# ProDoc_RiscArchive_SCH.net
KiCad netlist of a schematic drawn in EasyEDA Pro
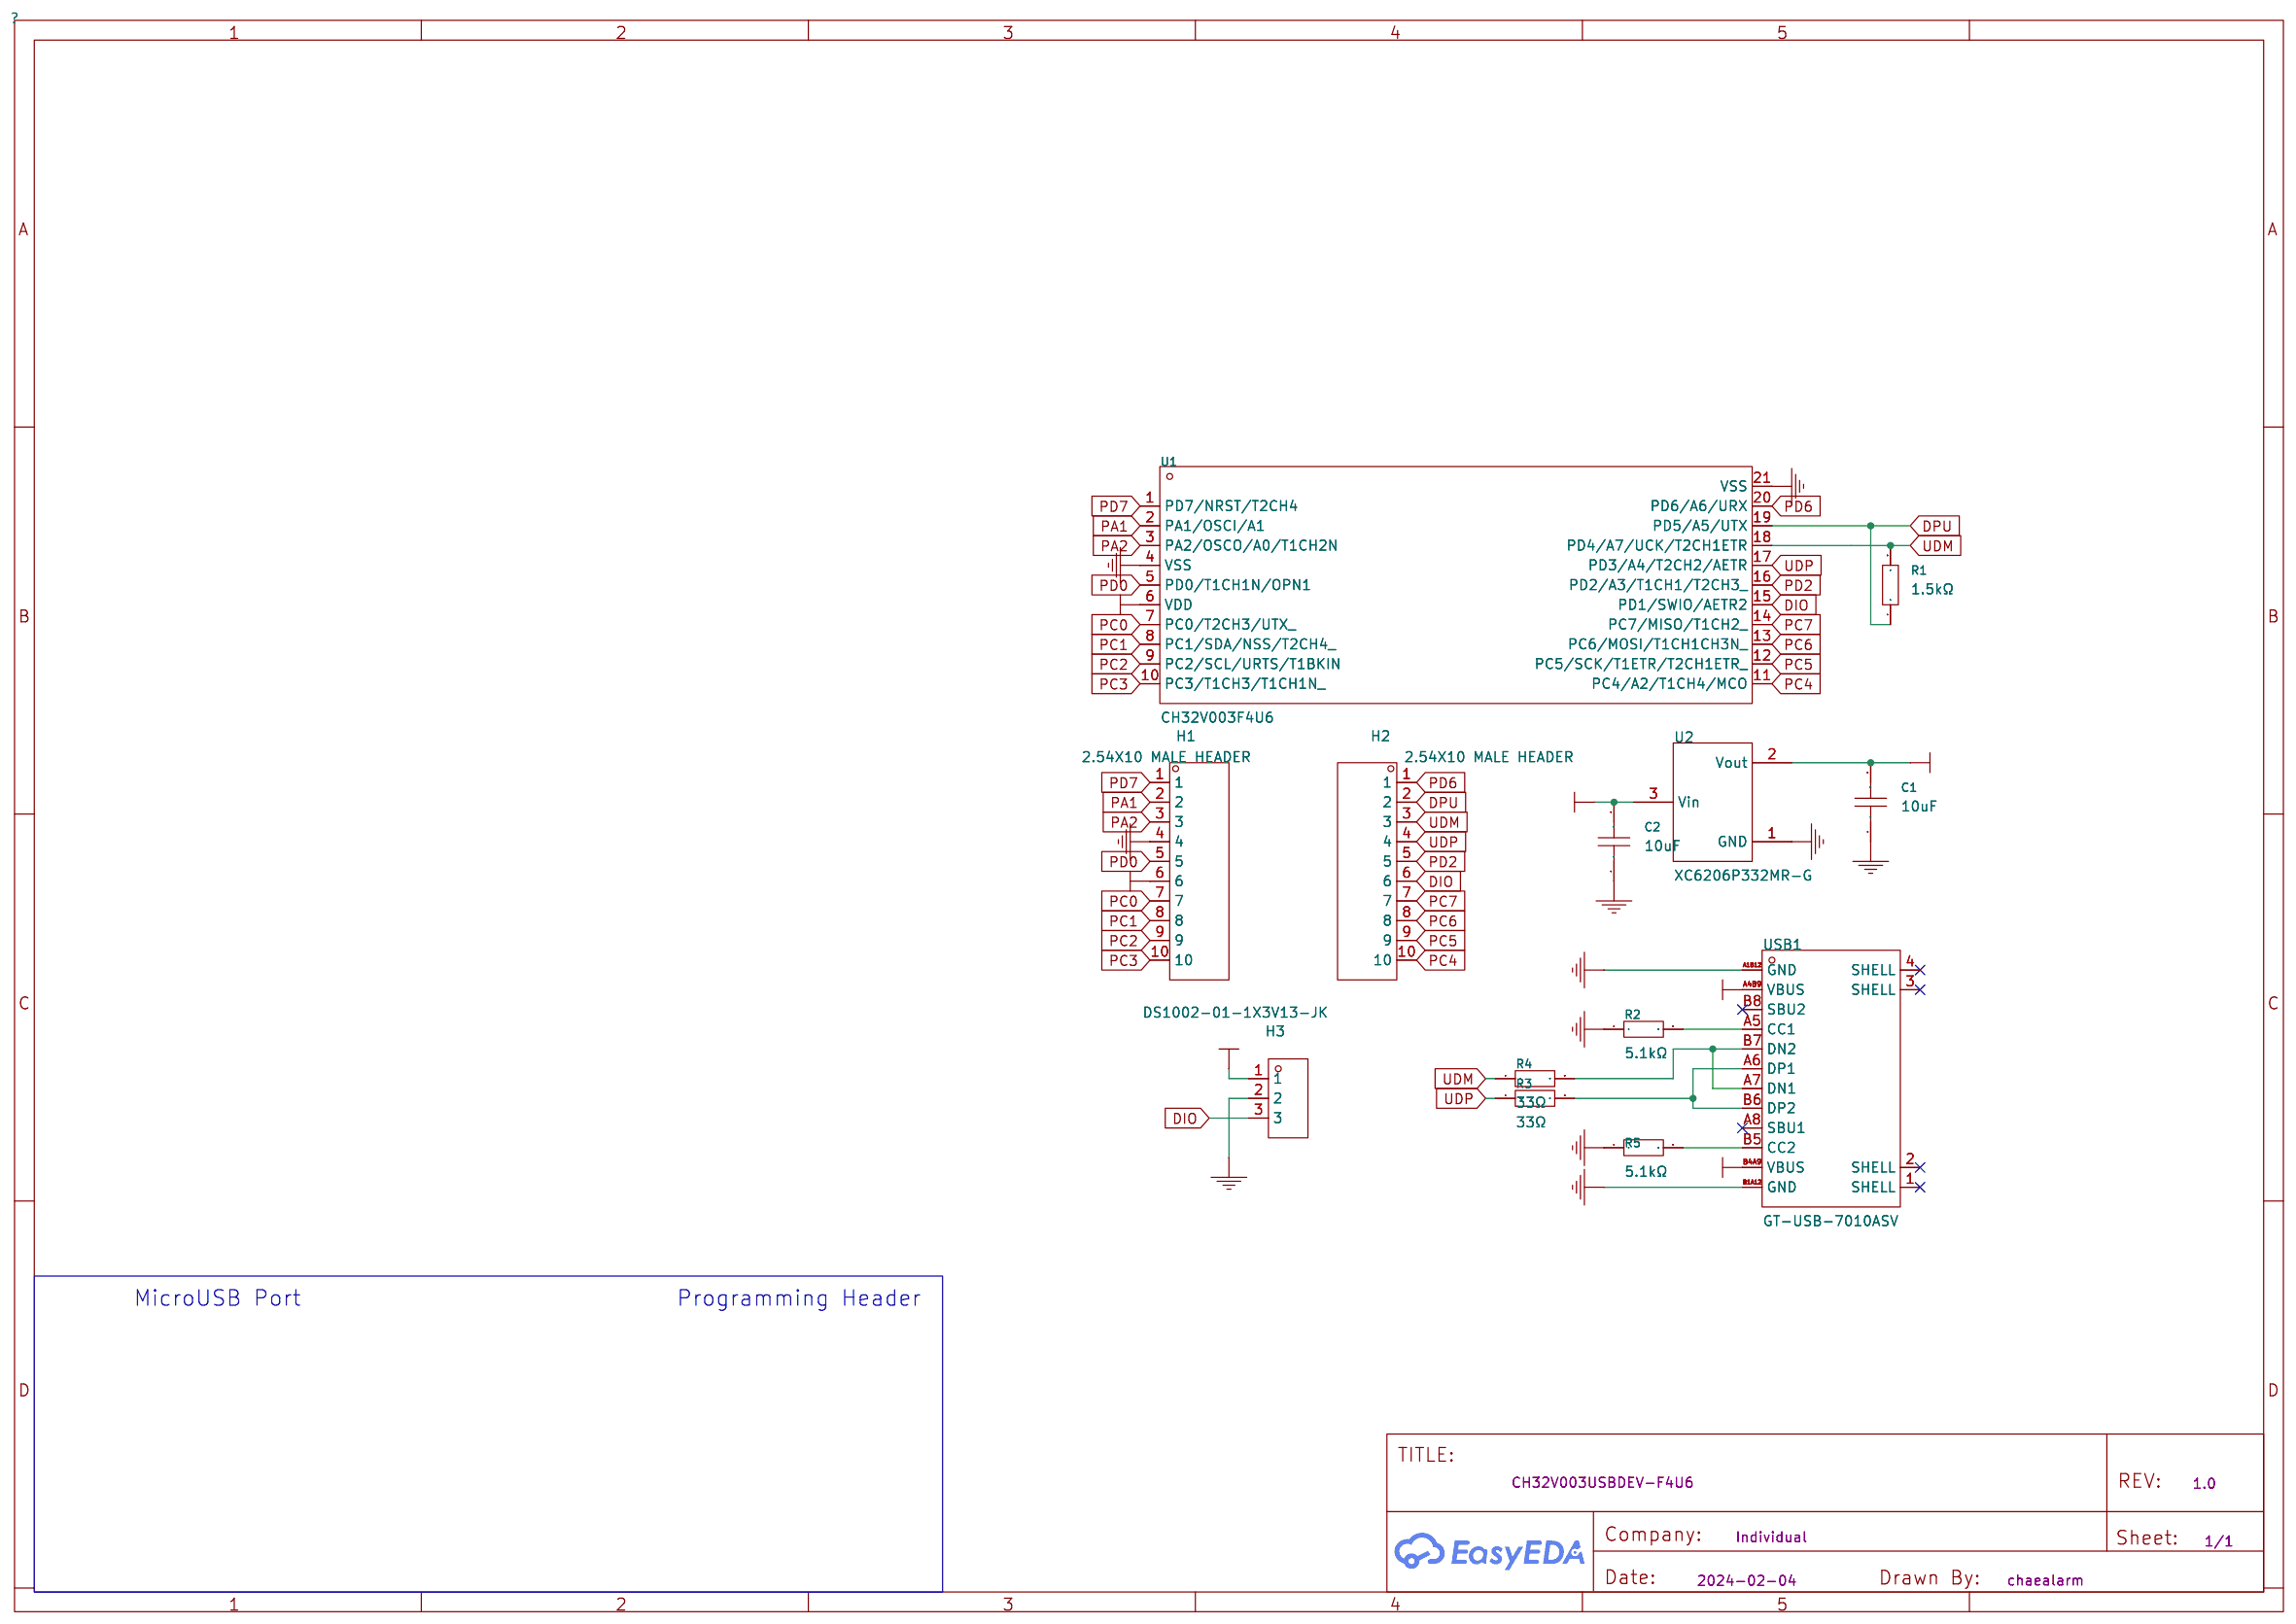
[diagram p0: schematic sheet]

(export (version "E")
  (design (tool "Eeschema 10.0.6"))
  (components
    (comp (ref "C1")
      (value "10uF")
      (footprint "easyedapro:C0603")
      (fields
        (field (name "Manufacturer Part") "CL10A106KP8NNNC")
        (field (name "Manufacturer") "SAMSUNG(三星)")
      )
      (libsource (lib "easyedapro") (part "CL10A106KP8NNNC"))
    )
    (comp (ref "C2")
      (value "10uF")
      (footprint "easyedapro:C0603")
      (fields
        (field (name "Manufacturer Part") "CL10A106KP8NNNC")
        (field (name "Manufacturer") "SAMSUNG(三星)")
      )
      (libsource (lib "easyedapro") (part "CL10A106KP8NNNC"))
    )
    (comp (ref "H1")
      (value "2.54X10 MALE HEADER")
      (footprint "easyedapro:footprint_8cc6")
      (fields
        (field (name "Manufacturer Part") "210S-1*11P L=11.6MMGold-plated black")
        (field (name "Manufacturer") "Ckmtw")
      )
      (libsource (lib "") (part "2.54X10 MALE HEADER_1"))
    )
    (comp (ref "H2")
      (value "2.54X10 MALE HEADER")
      (footprint "easyedapro:footprint_8cc6")
      (fields
        (field (name "Manufacturer Part") "210S-1*11P L=11.6MMGold-plated black")
        (field (name "Manufacturer") "Ckmtw")
      )
      (libsource (lib "easyedapro") (part "2.54X10 MALE HEADER"))
    )
    (comp (ref "H3")
      (value "DS1002-01-1X3V13-JK")
      (footprint "easyedapro:footprint_da6f")
      (fields
        (field (name "Manufacturer Part") "DS1002-01-1x3V13-JK")
        (field (name "Manufacturer") "CONNFLY")
      )
      (libsource (lib "easyedapro") (part "DS1002-01-1X3V13-JK"))
    )
    (comp (ref "R1")
      (value "1.5kΩ")
      (footprint "easyedapro:R0402")
      (fields
        (field (name "Manufacturer Part") "0402WGF1501TCE")
        (field (name "Manufacturer") "UNI-ROYAL(厚声)")
      )
      (libsource (lib "easyedapro") (part "0402WGF1501TCE"))
    )
    (comp (ref "R2")
      (value "5.1kΩ")
      (footprint "easyedapro:R0402")
      (fields
        (field (name "Manufacturer Part") "0402WGF5101TCE")
        (field (name "Manufacturer") "UNI-ROYAL(厚声)")
      )
      (libsource (lib "easyedapro") (part "0402WGF5101TCE"))
    )
    (comp (ref "R3")
      (value "33Ω")
      (footprint "easyedapro:R0402")
      (fields
        (field (name "Manufacturer Part") "0402WGF330JTCE")
        (field (name "Manufacturer") "UNI-ROYAL(厚声)")
      )
      (libsource (lib "easyedapro") (part "0402WGF330JTCE"))
    )
    (comp (ref "R4")
      (value "33Ω")
      (footprint "easyedapro:R0402")
      (fields
        (field (name "Manufacturer Part") "0402WGF330JTCE")
        (field (name "Manufacturer") "UNI-ROYAL(厚声)")
      )
      (libsource (lib "easyedapro") (part "0402WGF330JTCE"))
    )
    (comp (ref "R5")
      (value "5.1kΩ")
      (footprint "easyedapro:R0402")
      (fields
        (field (name "Manufacturer Part") "0402WGF5101TCE")
        (field (name "Manufacturer") "UNI-ROYAL(厚声)")
      )
      (libsource (lib "easyedapro") (part "0402WGF5101TCE"))
    )
    (comp (ref "U1")
      (value "CH32V003F4U6")
      (footprint "easyedapro:QFN-20_L3.0-W3.0-P0.40-TL-EP1.7")
      (fields (field (name "Manufacturer") "WCH(南京沁恒)"))
      (libsource (lib "easyedapro") (part "CH32V003F4U6"))
    )
    (comp (ref "U2")
      (value "XC6206P332MR-G")
      (footprint "easyedapro:SOT-23-3_L2.9-W1.6-P1.90-LS2.8-BR")
      (fields (field (name "Manufacturer") "TOREX(特瑞仕)"))
      (libsource (lib "easyedapro") (part "XC6206P332MR"))
    )
    (comp (ref "USB1")
      (value "GT-USB-7010ASV")
      (footprint "easyedapro:USB-C-SMD_G-SWITCH_GT-USB-7010ASV")
      (fields (field (name "Manufacturer") "G-Switch(品赞)"))
      (libsource (lib "easyedapro") (part "GT-USB-7010ASV"))
    )
  )
  (nets
    (net (code "1") (name "+3V3") (class "Default")
      (node (ref "C1") (pin "2") (pinfunction "2_2") (pintype "input"))
      (node (ref "H1") (pin "6") (pinfunction "6_6") (pintype "unspecified"))
      (node (ref "H3") (pin "1") (pinfunction "1_1") (pintype "unspecified"))
      (node (ref "U1") (pin "6") (pinfunction "VDD_6") (pintype "input"))
      (node (ref "U2") (pin "2") (pinfunction "Vout_2") (pintype "unspecified"))
    )
    (net (code "2") (name "+5V") (class "Default")
      (node (ref "C2") (pin "2") (pinfunction "2_2") (pintype "input"))
      (node (ref "U2") (pin "3") (pinfunction "Vin_3") (pintype "unspecified"))
      (node (ref "USB1") (pin "A4B9") (pinfunction "VBUS_A4B9") (pintype "unspecified"))
      (node (ref "USB1") (pin "B4A9") (pinfunction "VBUS_B4A9") (pintype "unspecified"))
    )
    (net (code "3") (name "DIO") (class "Default")
      (node (ref "H2") (pin "6") (pinfunction "6_6") (pintype "unspecified"))
      (node (ref "H3") (pin "3") (pinfunction "3_3") (pintype "unspecified"))
      (node (ref "U1") (pin "15") (pinfunction "PD1/SWIO/AETR2_15") (pintype "input"))
    )
    (net (code "4") (name "DPU") (class "Default")
      (node (ref "H2") (pin "2") (pinfunction "2_2") (pintype "unspecified"))
      (node (ref "R1") (pin "1") (pinfunction "1_1") (pintype "input"))
      (node (ref "U1") (pin "19") (pinfunction "PD5/A5/UTX_19") (pintype "input"))
    )
    (net (code "5") (name "GND") (class "Default")
      (node (ref "C1") (pin "1") (pinfunction "1_1") (pintype "input"))
      (node (ref "C2") (pin "1") (pinfunction "1_1") (pintype "input"))
      (node (ref "H1") (pin "4") (pinfunction "4_4") (pintype "unspecified"))
      (node (ref "H3") (pin "2") (pinfunction "2_2") (pintype "unspecified"))
      (node (ref "R2") (pin "1") (pinfunction "1_1") (pintype "input"))
      (node (ref "R5") (pin "1") (pinfunction "1_1") (pintype "input"))
      (node (ref "U1") (pin "21") (pinfunction "VSS_21") (pintype "input"))
      (node (ref "U1") (pin "4") (pinfunction "VSS_4") (pintype "input"))
      (node (ref "U2") (pin "1") (pinfunction "GND_1") (pintype "unspecified"))
      (node (ref "USB1") (pin "A1B12") (pinfunction "GND_A1B12") (pintype "unspecified"))
      (node (ref "USB1") (pin "B1A12") (pinfunction "GND_B1A12") (pintype "unspecified"))
    )
    (net (code "6") (name "Net-(USB1-CC1)") (class "Default")
      (node (ref "R2") (pin "2") (pinfunction "2_2") (pintype "input"))
      (node (ref "USB1") (pin "A5") (pinfunction "CC1_A5") (pintype "unspecified"))
    )
    (net (code "7") (name "Net-(USB1-CC2)") (class "Default")
      (node (ref "R5") (pin "2") (pinfunction "2_2") (pintype "input"))
      (node (ref "USB1") (pin "B5") (pinfunction "CC2_B5") (pintype "unspecified"))
    )
    (net (code "8") (name "Net-(USB1-DN1)") (class "Default")
      (node (ref "R4") (pin "2") (pinfunction "2_2") (pintype "input"))
      (node (ref "USB1") (pin "A7") (pinfunction "DN1_A7") (pintype "unspecified"))
      (node (ref "USB1") (pin "B7") (pinfunction "DN2_B7") (pintype "unspecified"))
    )
    (net (code "9") (name "Net-(USB1-DP1)") (class "Default")
      (node (ref "R3") (pin "2") (pinfunction "2_2") (pintype "input"))
      (node (ref "USB1") (pin "A6") (pinfunction "DP1_A6") (pintype "unspecified"))
      (node (ref "USB1") (pin "B6") (pinfunction "DP2_B6") (pintype "unspecified"))
    )
    (net (code "10") (name "PA1") (class "Default")
      (node (ref "H1") (pin "2") (pinfunction "2_2") (pintype "unspecified"))
      (node (ref "U1") (pin "2") (pinfunction "PA1/OSCI/A1_2") (pintype "input"))
    )
    (net (code "11") (name "PA2") (class "Default")
      (node (ref "H1") (pin "3") (pinfunction "3_3") (pintype "unspecified"))
      (node (ref "U1") (pin "3") (pinfunction "PA2/OSCO/A0/T1CH2N_3") (pintype "input"))
    )
    (net (code "12") (name "PC0") (class "Default")
      (node (ref "H1") (pin "7") (pinfunction "7_7") (pintype "unspecified"))
      (node (ref "U1") (pin "7") (pinfunction "PC0/T2CH3/UTX__7") (pintype "input"))
    )
    (net (code "13") (name "PC1") (class "Default")
      (node (ref "H1") (pin "8") (pinfunction "8_8") (pintype "unspecified"))
      (node (ref "U1") (pin "8") (pinfunction "PC1/SDA/NSS/T2CH4__8") (pintype "input"))
    )
    (net (code "14") (name "PC2") (class "Default")
      (node (ref "H1") (pin "9") (pinfunction "9_9") (pintype "unspecified"))
      (node (ref "U1") (pin "9") (pinfunction "PC2/SCL/URTS/T1BKIN_9") (pintype "input"))
    )
    (net (code "15") (name "PC3") (class "Default")
      (node (ref "H1") (pin "10") (pinfunction "10_10") (pintype "unspecified"))
      (node (ref "U1") (pin "10") (pinfunction "PC3/T1CH3/T1CH1N__10") (pintype "input"))
    )
    (net (code "16") (name "PC4") (class "Default")
      (node (ref "H2") (pin "10") (pinfunction "10_10") (pintype "unspecified"))
      (node (ref "U1") (pin "11") (pinfunction "PC4/A2/T1CH4/MCO_11") (pintype "input"))
    )
    (net (code "17") (name "PC5") (class "Default")
      (node (ref "H2") (pin "9") (pinfunction "9_9") (pintype "unspecified"))
      (node (ref "U1") (pin "12") (pinfunction "PC5/SCK/T1ETR/T2CH1ETR__12") (pintype "input"))
    )
    (net (code "18") (name "PC6") (class "Default")
      (node (ref "H2") (pin "8") (pinfunction "8_8") (pintype "unspecified"))
      (node (ref "U1") (pin "13") (pinfunction "PC6/MOSI/T1CH1CH3N__13") (pintype "input"))
    )
    (net (code "19") (name "PC7") (class "Default")
      (node (ref "H2") (pin "7") (pinfunction "7_7") (pintype "unspecified"))
      (node (ref "U1") (pin "14") (pinfunction "PC7/MISO/T1CH2__14") (pintype "input"))
    )
    (net (code "20") (name "PD0") (class "Default")
      (node (ref "H1") (pin "5") (pinfunction "5_5") (pintype "unspecified"))
      (node (ref "U1") (pin "5") (pinfunction "PD0/T1CH1N/OPN1_5") (pintype "input"))
    )
    (net (code "21") (name "PD2") (class "Default")
      (node (ref "H2") (pin "5") (pinfunction "5_5") (pintype "unspecified"))
      (node (ref "U1") (pin "16") (pinfunction "PD2/A3/T1CH1/T2CH3__16") (pintype "input"))
    )
    (net (code "22") (name "PD6") (class "Default")
      (node (ref "H2") (pin "1") (pinfunction "1_1") (pintype "unspecified"))
      (node (ref "U1") (pin "20") (pinfunction "PD6/A6/URX_20") (pintype "input"))
    )
    (net (code "23") (name "PD7") (class "Default")
      (node (ref "H1") (pin "1") (pinfunction "1_1") (pintype "unspecified"))
      (node (ref "U1") (pin "1") (pinfunction "PD7/NRST/T2CH4_1") (pintype "input"))
    )
    (net (code "24") (name "UDM") (class "Default")
      (node (ref "H2") (pin "3") (pinfunction "3_3") (pintype "unspecified"))
      (node (ref "R1") (pin "2") (pinfunction "2_2") (pintype "input"))
      (node (ref "R4") (pin "1") (pinfunction "1_1") (pintype "input"))
      (node (ref "U1") (pin "18") (pinfunction "PD4/A7/UCK/T2CH1ETR_18") (pintype "input"))
    )
    (net (code "25") (name "UDP") (class "Default")
      (node (ref "H2") (pin "4") (pinfunction "4_4") (pintype "unspecified"))
      (node (ref "R3") (pin "1") (pinfunction "1_1") (pintype "input"))
      (node (ref "U1") (pin "17") (pinfunction "PD3/A4/T2CH2/AETR_17") (pintype "input"))
    )
    (net (code "26") (name "unconnected-(USB1-SBU1-PadA8)") (class "Default")
      (node (ref "USB1") (pin "A8") (pinfunction "SBU1_A8") (pintype "unspecified+no_connect"))
    )
    (net (code "27") (name "unconnected-(USB1-SBU2-PadB8)") (class "Default")
      (node (ref "USB1") (pin "B8") (pinfunction "SBU2_B8") (pintype "unspecified+no_connect"))
    )
    (net (code "28") (name "unconnected-(USB1-SHELL-Pad1)") (class "Default")
      (node (ref "USB1") (pin "1") (pinfunction "SHELL_1") (pintype "unspecified+no_connect"))
    )
    (net (code "29") (name "unconnected-(USB1-SHELL-Pad2)") (class "Default")
      (node (ref "USB1") (pin "2") (pinfunction "SHELL_2") (pintype "unspecified+no_connect"))
    )
    (net (code "30") (name "unconnected-(USB1-SHELL-Pad3)") (class "Default")
      (node (ref "USB1") (pin "3") (pinfunction "SHELL_3") (pintype "unspecified+no_connect"))
    )
    (net (code "31") (name "unconnected-(USB1-SHELL-Pad4)") (class "Default")
      (node (ref "USB1") (pin "4") (pinfunction "SHELL_4") (pintype "unspecified+no_connect"))
    )
  )
)
